# Adafruit_STEMMA_Piezo_Driver_Amp.net
KiCad netlist of a schematic drawn in EAGLE
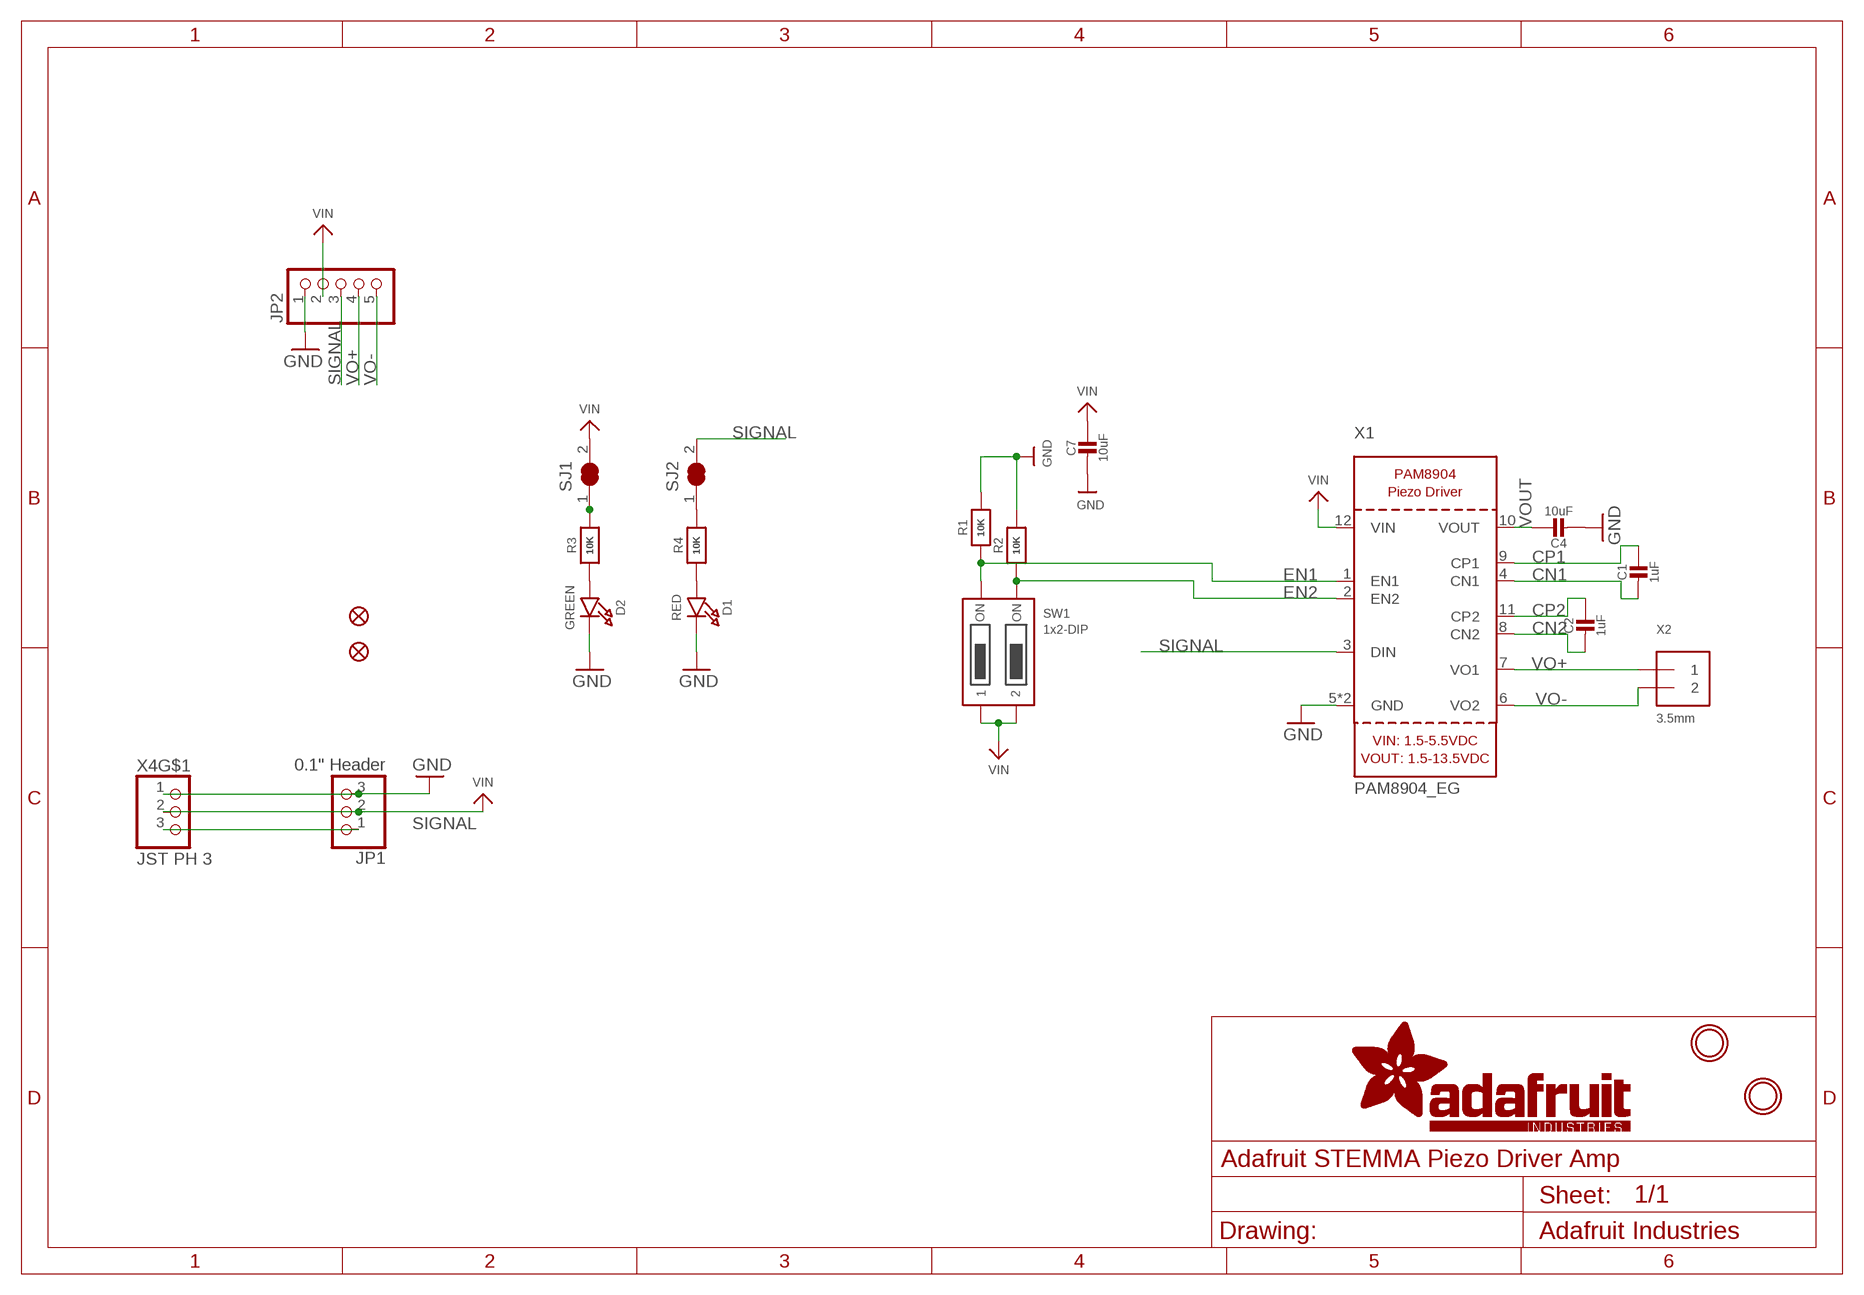
[diagram p0: schematic, sheet 1]

(export (version "E")
  (design (tool "Eeschema 10.0.6"))
  (components
    (comp (ref "C1")
      (value "1uF")
      (footprint "eagle-import:0603-NO")
      (libsource (lib "eagle-import") (part "CAP_CERAMIC0603_NO"))
    )
    (comp (ref "C2")
      (value "1uF")
      (footprint "eagle-import:0603-NO")
      (libsource (lib "eagle-import") (part "CAP_CERAMIC0603_NO"))
    )
    (comp (ref "C4")
      (value "10uF")
      (footprint "eagle-import:0805-NO")
      (libsource (lib "eagle-import") (part "CAP_CERAMIC0805-NOOUTLINE"))
    )
    (comp (ref "C7")
      (value "10uF")
      (footprint "eagle-import:0805-NO")
      (libsource (lib "eagle-import") (part "CAP_CERAMIC0805-NOOUTLINE"))
    )
    (comp (ref "D1")
      (value "RED")
      (footprint "eagle-import:CHIPLED_0603_NOOUTLINE")
      (libsource (lib "eagle-import") (part "LED0603_NOOUTLINE"))
    )
    (comp (ref "D2")
      (value "GREEN")
      (footprint "eagle-import:CHIPLED_0603_NOOUTLINE")
      (libsource (lib "eagle-import") (part "LED0603_NOOUTLINE"))
    )
    (comp (ref "FID2")
      (value "FIDUCIAL_1MM")
      (footprint "eagle-import:FIDUCIAL_1MM")
      (libsource (lib "eagle-import") (part "FIDUCIAL_1MM"))
    )
    (comp (ref "FID3")
      (value "FIDUCIAL_1MM")
      (footprint "eagle-import:FIDUCIAL_1MM")
      (libsource (lib "eagle-import") (part "FIDUCIAL_1MM"))
    )
    (comp (ref "JP1")
      (value "0.1\" Header")
      (footprint "eagle-import:1X03_OVAL")
      (libsource (lib "eagle-import") (part "HEADER-1X3"))
    )
    (comp (ref "JP2")
      (value "HEADER-1X570MIL")
      (footprint "eagle-import:1X05_ROUND_70")
      (libsource (lib "eagle-import") (part "HEADER-1X570MIL"))
    )
    (comp (ref "R1")
      (value "10K")
      (footprint "eagle-import:0603-NO")
      (libsource (lib "eagle-import") (part "RESISTOR_0603_NOOUT"))
    )
    (comp (ref "R2")
      (value "10K")
      (footprint "eagle-import:0603-NO")
      (libsource (lib "eagle-import") (part "RESISTOR_0603_NOOUT"))
    )
    (comp (ref "R3")
      (value "10K")
      (footprint "eagle-import:0603-NO")
      (libsource (lib "eagle-import") (part "RESISTOR_0603_NOOUT"))
    )
    (comp (ref "R4")
      (value "10K")
      (footprint "eagle-import:0603-NO")
      (libsource (lib "eagle-import") (part "RESISTOR_0603_NOOUT"))
    )
    (comp (ref "SJ1")
      (value "SOLDERJUMPER_CLOSED")
      (footprint "eagle-import:SOLDERJUMPER_CLOSEDWIRE")
      (libsource (lib "eagle-import") (part "SOLDERJUMPER_CLOSED"))
    )
    (comp (ref "SJ2")
      (value "SOLDERJUMPER_CLOSED")
      (footprint "eagle-import:SOLDERJUMPER_CLOSEDWIRE")
      (libsource (lib "eagle-import") (part "SOLDERJUMPER_CLOSED"))
    )
    (comp (ref "SW1")
      (value "1x2-DIP")
      (footprint "eagle-import:DIPSWITCH_2PIN")
      (libsource (lib "eagle-import") (part "DIPSWITCH_2PIN"))
    )
    (comp (ref "U$1")
      (value "MOUNTINGHOLE2.5")
      (footprint "eagle-import:MOUNTINGHOLE_2.5_PLATED")
      (libsource (lib "eagle-import") (part "MOUNTINGHOLE2.5"))
    )
    (comp (ref "U$8")
      (value "MOUNTINGHOLE2.5")
      (footprint "eagle-import:MOUNTINGHOLE_2.5_PLATED")
      (libsource (lib "eagle-import") (part "MOUNTINGHOLE2.5"))
    )
    (comp (ref "X1")
      (value "PAM8904_EG")
      (footprint "eagle-import:QFN12-2MM")
      (libsource (lib "eagle-import") (part "PAM8904_EG"))
    )
    (comp (ref "X2")
      (value "3.5mm")
      (footprint "eagle-import:TERMBLOCK_1X2-3.5MM")
      (libsource (lib "eagle-import") (part "TERMBLOCK_1X2_3.5MM"))
    )
    (comp (ref "X4")
      (value "JST PH 3")
      (footprint "eagle-import:JSTPH3")
      (libsource (lib "eagle-import") (part "CON_JST_PH_3PIN"))
    )
  )
  (nets
    (net (code "1") (name "/CN1") (class "Default")
      (node (ref "C1") (pin "2") (pinfunction "2_2") (pintype "passive"))
      (node (ref "X1") (pin "4") (pinfunction "CN1_4") (pintype "output"))
    )
    (net (code "2") (name "/CN2") (class "Default")
      (node (ref "C2") (pin "2") (pinfunction "2_2") (pintype "passive"))
      (node (ref "X1") (pin "8") (pinfunction "CN2_8") (pintype "output"))
    )
    (net (code "3") (name "/CP1") (class "Default")
      (node (ref "C1") (pin "1") (pinfunction "1_1") (pintype "passive"))
      (node (ref "X1") (pin "9") (pinfunction "CP1_9") (pintype "output"))
    )
    (net (code "4") (name "/CP2") (class "Default")
      (node (ref "C2") (pin "1") (pinfunction "1_1") (pintype "passive"))
      (node (ref "X1") (pin "11") (pinfunction "CP2_11") (pintype "output"))
    )
    (net (code "5") (name "/EN1") (class "Default")
      (node (ref "R1") (pin "1") (pinfunction "1_1") (pintype "passive"))
      (node (ref "SW1") (pin "1ON") (pinfunction "1ON_1ON") (pintype "bidirectional"))
      (node (ref "X1") (pin "1") (pinfunction "EN1_1") (pintype "input"))
    )
    (net (code "6") (name "/EN2") (class "Default")
      (node (ref "R2") (pin "1") (pinfunction "1_1") (pintype "passive"))
      (node (ref "SW1") (pin "2ON") (pinfunction "2ON_2ON") (pintype "bidirectional"))
      (node (ref "X1") (pin "2") (pinfunction "EN2_2") (pintype "input"))
    )
    (net (code "7") (name "/SIGNAL") (class "Default")
      (node (ref "JP1") (pin "1") (pinfunction "1_1") (pintype "passive"))
      (node (ref "JP2") (pin "3") (pinfunction "3_3") (pintype "passive"))
      (node (ref "SJ2") (pin "2") (pinfunction "2_2") (pintype "passive"))
      (node (ref "X1") (pin "3") (pinfunction "DIN_3") (pintype "input"))
      (node (ref "X4") (pin "3") (pinfunction "3_3") (pintype "passive"))
    )
    (net (code "8") (name "/VO+") (class "Default")
      (node (ref "JP2") (pin "4") (pinfunction "4_4") (pintype "passive"))
      (node (ref "X1") (pin "7") (pinfunction "VO1_7") (pintype "output"))
      (node (ref "X2") (pin "1") (pinfunction "1_1") (pintype "passive"))
    )
    (net (code "9") (name "/VO-") (class "Default")
      (node (ref "JP2") (pin "5") (pinfunction "5_5") (pintype "passive"))
      (node (ref "X1") (pin "6") (pinfunction "VO2_6") (pintype "output"))
      (node (ref "X2") (pin "2") (pinfunction "2_2") (pintype "passive"))
    )
    (net (code "10") (name "/VOUT") (class "Default")
      (node (ref "C4") (pin "1") (pinfunction "1_1") (pintype "passive"))
      (node (ref "X1") (pin "10") (pinfunction "VOUT_10") (pintype "output"))
    )
    (net (code "11") (name "GND") (class "Default")
      (node (ref "C4") (pin "2") (pinfunction "2_2") (pintype "passive"))
      (node (ref "C7") (pin "2") (pinfunction "2_2") (pintype "passive"))
      (node (ref "D1") (pin "C") (pinfunction "C_C") (pintype "passive"))
      (node (ref "D2") (pin "C") (pinfunction "C_C") (pintype "passive"))
      (node (ref "JP1") (pin "3") (pinfunction "3_3") (pintype "passive"))
      (node (ref "JP2") (pin "1") (pinfunction "1_1") (pintype "passive"))
      (node (ref "R1") (pin "2") (pinfunction "2_2") (pintype "passive"))
      (node (ref "R2") (pin "2") (pinfunction "2_2") (pintype "passive"))
      (node (ref "X1") (pin "5") (pinfunction "GND_5") (pintype "power_in"))
      (node (ref "X1") (pin "MT") (pinfunction "GND_MT") (pintype "power_in"))
      (node (ref "X4") (pin "1") (pinfunction "1_1") (pintype "passive"))
    )
    (net (code "12") (name "Net-(D1-PadA)") (class "Default")
      (node (ref "D1") (pin "A") (pinfunction "A_A") (pintype "passive"))
      (node (ref "R4") (pin "1") (pinfunction "1_1") (pintype "passive"))
    )
    (net (code "13") (name "Net-(D2-PadA)") (class "Default")
      (node (ref "D2") (pin "A") (pinfunction "A_A") (pintype "passive"))
      (node (ref "R3") (pin "1") (pinfunction "1_1") (pintype "passive"))
    )
    (net (code "14") (name "Net-(R3-Pad2)") (class "Default")
      (node (ref "R3") (pin "2") (pinfunction "2_2") (pintype "passive"))
      (node (ref "SJ1") (pin "1") (pinfunction "1_1") (pintype "passive"))
    )
    (net (code "15") (name "Net-(R4-Pad2)") (class "Default")
      (node (ref "R4") (pin "2") (pinfunction "2_2") (pintype "passive"))
      (node (ref "SJ2") (pin "1") (pinfunction "1_1") (pintype "passive"))
    )
    (net (code "16") (name "VIN") (class "Default")
      (node (ref "C7") (pin "1") (pinfunction "1_1") (pintype "passive"))
      (node (ref "JP1") (pin "2") (pinfunction "2_2") (pintype "passive"))
      (node (ref "JP2") (pin "2") (pinfunction "2_2") (pintype "passive"))
      (node (ref "SJ1") (pin "2") (pinfunction "2_2") (pintype "passive"))
      (node (ref "SW1") (pin "1OFF") (pinfunction "1OFF_1OFF") (pintype "bidirectional"))
      (node (ref "SW1") (pin "2OFF") (pinfunction "2OFF_2OFF") (pintype "bidirectional"))
      (node (ref "X1") (pin "12") (pinfunction "VIN_12") (pintype "power_in"))
      (node (ref "X4") (pin "2") (pinfunction "2_2") (pintype "passive"))
    )
  )
)
